# 4ButtonSwitch_ItsyBitsyM0_Rev1_1.net
KiCad netlist of a schematic drawn in EAGLE
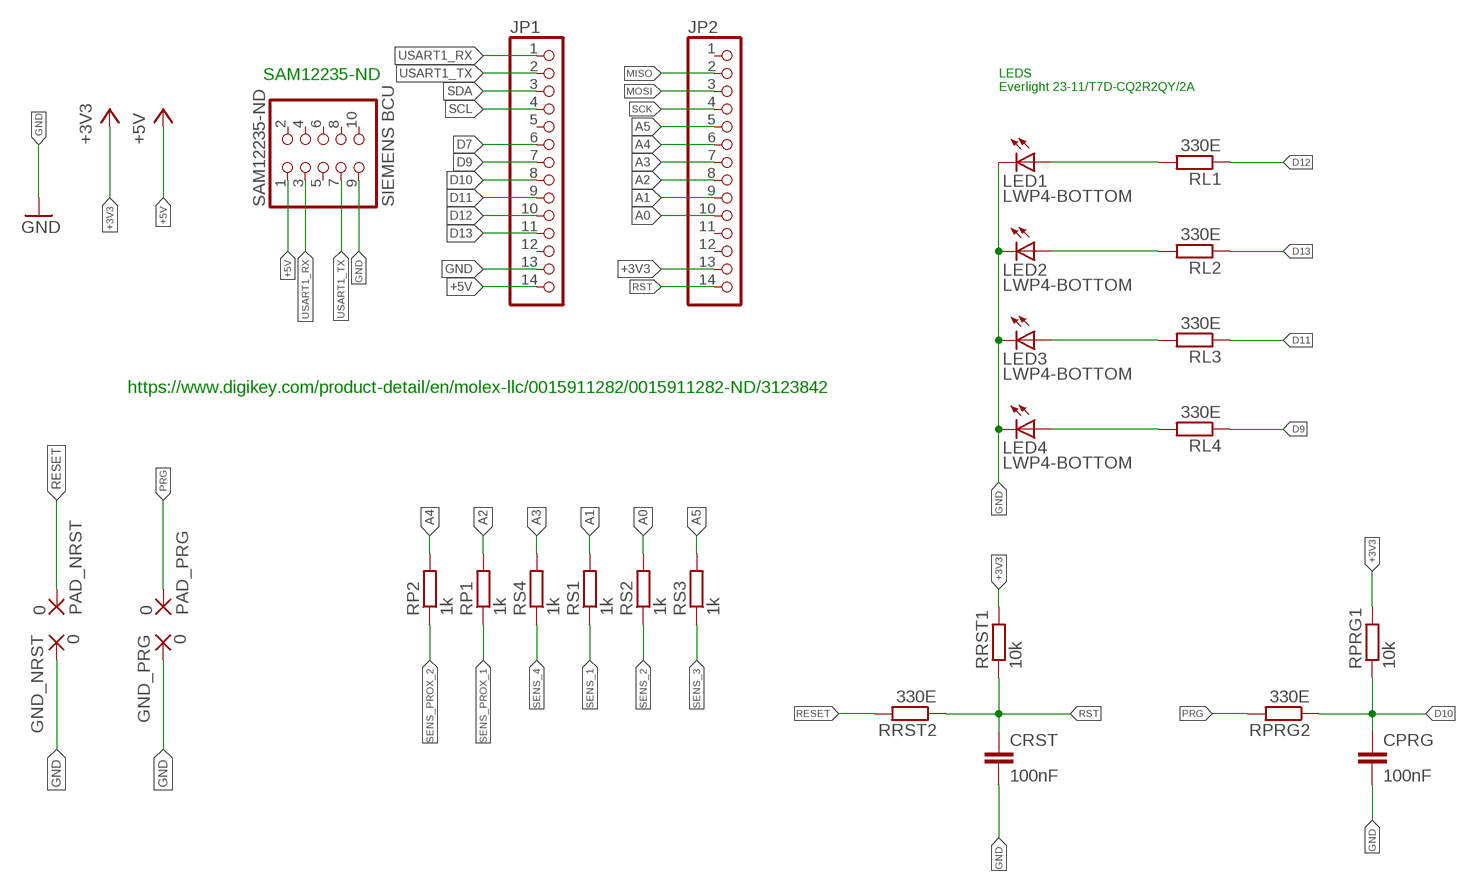
[diagram p0: schematic, sheet 1]

(export (version "E")
  (design (tool "Eeschema 10.0.6"))
  (components
    (comp (ref "CPRG")
      (value "100nF")
      (footprint "eagle-import:C1206")
      (libsource (lib "eagle-import") (part "C-EUC1206"))
    )
    (comp (ref "CRST")
      (value "100nF")
      (footprint "eagle-import:C1206")
      (libsource (lib "eagle-import") (part "C-EUC1206"))
    )
    (comp (ref "GND_NRST")
      (value "0")
      (footprint "eagle-import:SMD2,54-5,08")
      (libsource (lib "eagle-import") (part "SMD5"))
    )
    (comp (ref "GND_PRG")
      (value "0")
      (footprint "eagle-import:SMD2,54-5,08")
      (libsource (lib "eagle-import") (part "SMD5"))
    )
    (comp (ref "JP1")
      (value "PINHD-1X141X14_SMT")
      (footprint "eagle-import:1X14_SMT")
      (libsource (lib "eagle-import") (part "PINHD-1X141X14_SMT"))
    )
    (comp (ref "JP2")
      (value "PINHD-1X141X14_SMT")
      (footprint "eagle-import:1X14_SMT")
      (libsource (lib "eagle-import") (part "PINHD-1X141X14_SMT"))
    )
    (comp (ref "LED1")
      (value "LWP4-BOTTOM")
      (footprint "eagle-import:P47F-BOTTOM")
      (libsource (lib "eagle-import") (part "P4-BOTTOMLW"))
    )
    (comp (ref "LED2")
      (value "LWP4-BOTTOM")
      (footprint "eagle-import:P47F-BOTTOM")
      (libsource (lib "eagle-import") (part "P4-BOTTOMLW"))
    )
    (comp (ref "LED3")
      (value "LWP4-BOTTOM")
      (footprint "eagle-import:P47F-BOTTOM")
      (libsource (lib "eagle-import") (part "P4-BOTTOMLW"))
    )
    (comp (ref "LED4")
      (value "LWP4-BOTTOM")
      (footprint "eagle-import:P47F-BOTTOM")
      (libsource (lib "eagle-import") (part "P4-BOTTOMLW"))
    )
    (comp (ref "PAD_NRST")
      (value "0")
      (footprint "eagle-import:SMD2,54-5,08")
      (libsource (lib "eagle-import") (part "SMD5"))
    )
    (comp (ref "PAD_PRG")
      (value "0")
      (footprint "eagle-import:SMD2,54-5,08")
      (libsource (lib "eagle-import") (part "SMD5"))
    )
    (comp (ref "RL1")
      (value "330E")
      (footprint "eagle-import:R1206")
      (libsource (lib "eagle-import") (part "R-EU_R1206"))
    )
    (comp (ref "RL2")
      (value "330E")
      (footprint "eagle-import:R1206")
      (libsource (lib "eagle-import") (part "R-EU_R1206"))
    )
    (comp (ref "RL3")
      (value "330E")
      (footprint "eagle-import:R1206")
      (libsource (lib "eagle-import") (part "R-EU_R1206"))
    )
    (comp (ref "RL4")
      (value "330E")
      (footprint "eagle-import:R1206")
      (libsource (lib "eagle-import") (part "R-EU_R1206"))
    )
    (comp (ref "RP1")
      (value "1k")
      (footprint "eagle-import:R1206")
      (libsource (lib "eagle-import") (part "R-EU_R1206"))
    )
    (comp (ref "RP2")
      (value "1k")
      (footprint "eagle-import:R1206")
      (libsource (lib "eagle-import") (part "R-EU_R1206"))
    )
    (comp (ref "RPRG1")
      (value "10k")
      (footprint "eagle-import:R1206")
      (libsource (lib "eagle-import") (part "R-EU_R1206"))
    )
    (comp (ref "RPRG2")
      (value "330E")
      (footprint "eagle-import:R1206")
      (libsource (lib "eagle-import") (part "R-EU_R1206"))
    )
    (comp (ref "RRST1")
      (value "10k")
      (footprint "eagle-import:R1206")
      (libsource (lib "eagle-import") (part "R-EU_R1206"))
    )
    (comp (ref "RRST2")
      (value "330E")
      (footprint "eagle-import:R1206")
      (libsource (lib "eagle-import") (part "R-EU_R1206"))
    )
    (comp (ref "RS1")
      (value "1k")
      (footprint "eagle-import:R1206")
      (libsource (lib "eagle-import") (part "R-EU_R1206"))
    )
    (comp (ref "RS2")
      (value "1k")
      (footprint "eagle-import:R1206")
      (libsource (lib "eagle-import") (part "R-EU_R1206"))
    )
    (comp (ref "RS3")
      (value "1k")
      (footprint "eagle-import:R1206")
      (libsource (lib "eagle-import") (part "R-EU_R1206"))
    )
    (comp (ref "RS4")
      (value "1k")
      (footprint "eagle-import:R1206")
      (libsource (lib "eagle-import") (part "R-EU_R1206"))
    )
    (comp (ref "SAM12235-ND")
      (value "SIEMENS BCU")
      (footprint "eagle-import:2X05SMD")
      (libsource (lib "eagle-import") (part "PINHD-2X5_2.54-SMD"))
    )
  )
  (nets
    (net (code "1") (name "+3V3") (class "Default")
      (node (ref "JP2") (pin "13") (pinfunction "13_13") (pintype "passive"))
      (node (ref "RPRG1") (pin "2") (pinfunction "2_2") (pintype "passive"))
      (node (ref "RRST1") (pin "2") (pinfunction "2_2") (pintype "passive"))
    )
    (net (code "2") (name "+5V") (class "Default")
      (node (ref "JP1") (pin "14") (pinfunction "14_14") (pintype "passive"))
      (node (ref "SAM12235-ND") (pin "1") (pinfunction "1_1") (pintype "passive"))
    )
    (net (code "3") (name "A0") (class "Default")
      (node (ref "JP2") (pin "10") (pinfunction "10_10") (pintype "passive"))
      (node (ref "RS2") (pin "2") (pinfunction "2_2") (pintype "passive"))
    )
    (net (code "4") (name "A1") (class "Default")
      (node (ref "JP2") (pin "9") (pinfunction "9_9") (pintype "passive"))
      (node (ref "RS1") (pin "2") (pinfunction "2_2") (pintype "passive"))
    )
    (net (code "5") (name "A2") (class "Default")
      (node (ref "JP2") (pin "8") (pinfunction "8_8") (pintype "passive"))
      (node (ref "RP1") (pin "2") (pinfunction "2_2") (pintype "passive"))
    )
    (net (code "6") (name "A3") (class "Default")
      (node (ref "JP2") (pin "7") (pinfunction "7_7") (pintype "passive"))
      (node (ref "RS4") (pin "2") (pinfunction "2_2") (pintype "passive"))
    )
    (net (code "7") (name "A4") (class "Default")
      (node (ref "JP2") (pin "6") (pinfunction "6_6") (pintype "passive"))
      (node (ref "RP2") (pin "2") (pinfunction "2_2") (pintype "passive"))
    )
    (net (code "8") (name "A5") (class "Default")
      (node (ref "JP2") (pin "5") (pinfunction "5_5") (pintype "passive"))
      (node (ref "RS3") (pin "2") (pinfunction "2_2") (pintype "passive"))
    )
    (net (code "9") (name "D7") (class "Default")
      (node (ref "JP1") (pin "6") (pinfunction "6_6") (pintype "passive"))
    )
    (net (code "10") (name "D9") (class "Default")
      (node (ref "JP1") (pin "7") (pinfunction "7_7") (pintype "passive"))
      (node (ref "RL4") (pin "1") (pinfunction "1_1") (pintype "passive"))
    )
    (net (code "11") (name "D10") (class "Default")
      (node (ref "CPRG") (pin "1") (pinfunction "1_1") (pintype "passive"))
      (node (ref "JP1") (pin "8") (pinfunction "8_8") (pintype "passive"))
      (node (ref "RPRG1") (pin "1") (pinfunction "1_1") (pintype "passive"))
      (node (ref "RPRG2") (pin "1") (pinfunction "1_1") (pintype "passive"))
    )
    (net (code "12") (name "D11") (class "Default")
      (node (ref "JP1") (pin "9") (pinfunction "9_9") (pintype "passive"))
      (node (ref "RL3") (pin "1") (pinfunction "1_1") (pintype "passive"))
    )
    (net (code "13") (name "D12") (class "Default")
      (node (ref "JP1") (pin "10") (pinfunction "10_10") (pintype "passive"))
      (node (ref "RL1") (pin "1") (pinfunction "1_1") (pintype "passive"))
    )
    (net (code "14") (name "D13") (class "Default")
      (node (ref "JP1") (pin "11") (pinfunction "11_11") (pintype "passive"))
      (node (ref "RL2") (pin "1") (pinfunction "1_1") (pintype "passive"))
    )
    (net (code "15") (name "GND") (class "Default")
      (node (ref "CPRG") (pin "2") (pinfunction "2_2") (pintype "passive"))
      (node (ref "CRST") (pin "2") (pinfunction "2_2") (pintype "passive"))
      (node (ref "GND_NRST") (pin "1") (pinfunction "P_1") (pintype "passive"))
      (node (ref "GND_PRG") (pin "1") (pinfunction "P_1") (pintype "passive"))
      (node (ref "JP1") (pin "13") (pinfunction "13_13") (pintype "passive"))
      (node (ref "LED1") (pin "C") (pinfunction "C_C") (pintype "passive"))
      (node (ref "LED2") (pin "C") (pinfunction "C_C") (pintype "passive"))
      (node (ref "LED3") (pin "C") (pinfunction "C_C") (pintype "passive"))
      (node (ref "LED4") (pin "C") (pinfunction "C_C") (pintype "passive"))
      (node (ref "SAM12235-ND") (pin "9") (pinfunction "9_9") (pintype "passive"))
    )
    (net (code "16") (name "MISO") (class "Default")
      (node (ref "JP2") (pin "2") (pinfunction "2_2") (pintype "passive"))
    )
    (net (code "17") (name "MOSI") (class "Default")
      (node (ref "JP2") (pin "3") (pinfunction "3_3") (pintype "passive"))
    )
    (net (code "18") (name "Net-(LED1-PadA)") (class "Default")
      (node (ref "LED1") (pin "A") (pinfunction "A_A") (pintype "passive"))
      (node (ref "RL1") (pin "2") (pinfunction "2_2") (pintype "passive"))
    )
    (net (code "19") (name "Net-(LED2-PadA)") (class "Default")
      (node (ref "LED2") (pin "A") (pinfunction "A_A") (pintype "passive"))
      (node (ref "RL2") (pin "2") (pinfunction "2_2") (pintype "passive"))
    )
    (net (code "20") (name "Net-(LED3-PadA)") (class "Default")
      (node (ref "LED3") (pin "A") (pinfunction "A_A") (pintype "passive"))
      (node (ref "RL3") (pin "2") (pinfunction "2_2") (pintype "passive"))
    )
    (net (code "21") (name "Net-(LED4-PadA)") (class "Default")
      (node (ref "LED4") (pin "A") (pinfunction "A_A") (pintype "passive"))
      (node (ref "RL4") (pin "2") (pinfunction "2_2") (pintype "passive"))
    )
    (net (code "22") (name "PRG") (class "Default")
      (node (ref "PAD_PRG") (pin "1") (pinfunction "P_1") (pintype "passive"))
      (node (ref "RPRG2") (pin "2") (pinfunction "2_2") (pintype "passive"))
    )
    (net (code "23") (name "RESET") (class "Default")
      (node (ref "PAD_NRST") (pin "1") (pinfunction "P_1") (pintype "passive"))
      (node (ref "RRST2") (pin "2") (pinfunction "2_2") (pintype "passive"))
    )
    (net (code "24") (name "RST") (class "Default")
      (node (ref "CRST") (pin "1") (pinfunction "1_1") (pintype "passive"))
      (node (ref "JP2") (pin "14") (pinfunction "14_14") (pintype "passive"))
      (node (ref "RRST1") (pin "1") (pinfunction "1_1") (pintype "passive"))
      (node (ref "RRST2") (pin "1") (pinfunction "1_1") (pintype "passive"))
    )
    (net (code "25") (name "SCK") (class "Default")
      (node (ref "JP2") (pin "4") (pinfunction "4_4") (pintype "passive"))
    )
    (net (code "26") (name "SCL") (class "Default")
      (node (ref "JP1") (pin "4") (pinfunction "4_4") (pintype "passive"))
    )
    (net (code "27") (name "SDA") (class "Default")
      (node (ref "JP1") (pin "3") (pinfunction "3_3") (pintype "passive"))
    )
    (net (code "28") (name "SENS_1") (class "Default")
      (node (ref "RS1") (pin "1") (pinfunction "1_1") (pintype "passive"))
    )
    (net (code "29") (name "SENS_2") (class "Default")
      (node (ref "RS2") (pin "1") (pinfunction "1_1") (pintype "passive"))
    )
    (net (code "30") (name "SENS_3") (class "Default")
      (node (ref "RS3") (pin "1") (pinfunction "1_1") (pintype "passive"))
    )
    (net (code "31") (name "SENS_4") (class "Default")
      (node (ref "RS4") (pin "1") (pinfunction "1_1") (pintype "passive"))
    )
    (net (code "32") (name "SENS_PROX_1") (class "Default")
      (node (ref "RP1") (pin "1") (pinfunction "1_1") (pintype "passive"))
    )
    (net (code "33") (name "SENS_PROX_2") (class "Default")
      (node (ref "RP2") (pin "1") (pinfunction "1_1") (pintype "passive"))
    )
    (net (code "34") (name "USART1_RX") (class "Default")
      (node (ref "JP1") (pin "1") (pinfunction "1_1") (pintype "passive"))
      (node (ref "SAM12235-ND") (pin "3") (pinfunction "3_3") (pintype "passive"))
    )
    (net (code "35") (name "USART1_TX") (class "Default")
      (node (ref "JP1") (pin "2") (pinfunction "2_2") (pintype "passive"))
      (node (ref "SAM12235-ND") (pin "7") (pinfunction "7_7") (pintype "passive"))
    )
    (net (code "36") (name "unconnected-(JP1-Pad5)") (class "Default")
      (node (ref "JP1") (pin "5") (pinfunction "5_5") (pintype "passive"))
    )
    (net (code "37") (name "unconnected-(JP1-Pad12)") (class "Default")
      (node (ref "JP1") (pin "12") (pinfunction "12_12") (pintype "passive"))
    )
    (net (code "38") (name "unconnected-(JP2-Pad1)") (class "Default")
      (node (ref "JP2") (pin "1") (pinfunction "1_1") (pintype "passive"))
    )
    (net (code "39") (name "unconnected-(JP2-Pad11)") (class "Default")
      (node (ref "JP2") (pin "11") (pinfunction "11_11") (pintype "passive"))
    )
    (net (code "40") (name "unconnected-(JP2-Pad12)") (class "Default")
      (node (ref "JP2") (pin "12") (pinfunction "12_12") (pintype "passive"))
    )
    (net (code "41") (name "unconnected-(SAM12235-ND-Pad2)") (class "Default")
      (node (ref "SAM12235-ND") (pin "2") (pinfunction "2_2") (pintype "passive"))
    )
    (net (code "42") (name "unconnected-(SAM12235-ND-Pad4)") (class "Default")
      (node (ref "SAM12235-ND") (pin "4") (pinfunction "4_4") (pintype "passive"))
    )
    (net (code "43") (name "unconnected-(SAM12235-ND-Pad5)") (class "Default")
      (node (ref "SAM12235-ND") (pin "5") (pinfunction "5_5") (pintype "passive"))
    )
    (net (code "44") (name "unconnected-(SAM12235-ND-Pad6)") (class "Default")
      (node (ref "SAM12235-ND") (pin "6") (pinfunction "6_6") (pintype "passive"))
    )
    (net (code "45") (name "unconnected-(SAM12235-ND-Pad8)") (class "Default")
      (node (ref "SAM12235-ND") (pin "8") (pinfunction "8_8") (pintype "passive"))
    )
    (net (code "46") (name "unconnected-(SAM12235-ND-Pad10)") (class "Default")
      (node (ref "SAM12235-ND") (pin "10") (pinfunction "10_10") (pintype "passive"))
    )
  )
)
